# SCH_power_supply_7805_2026-06-21.net
KiCad netlist of a schematic drawn in EasyEDA
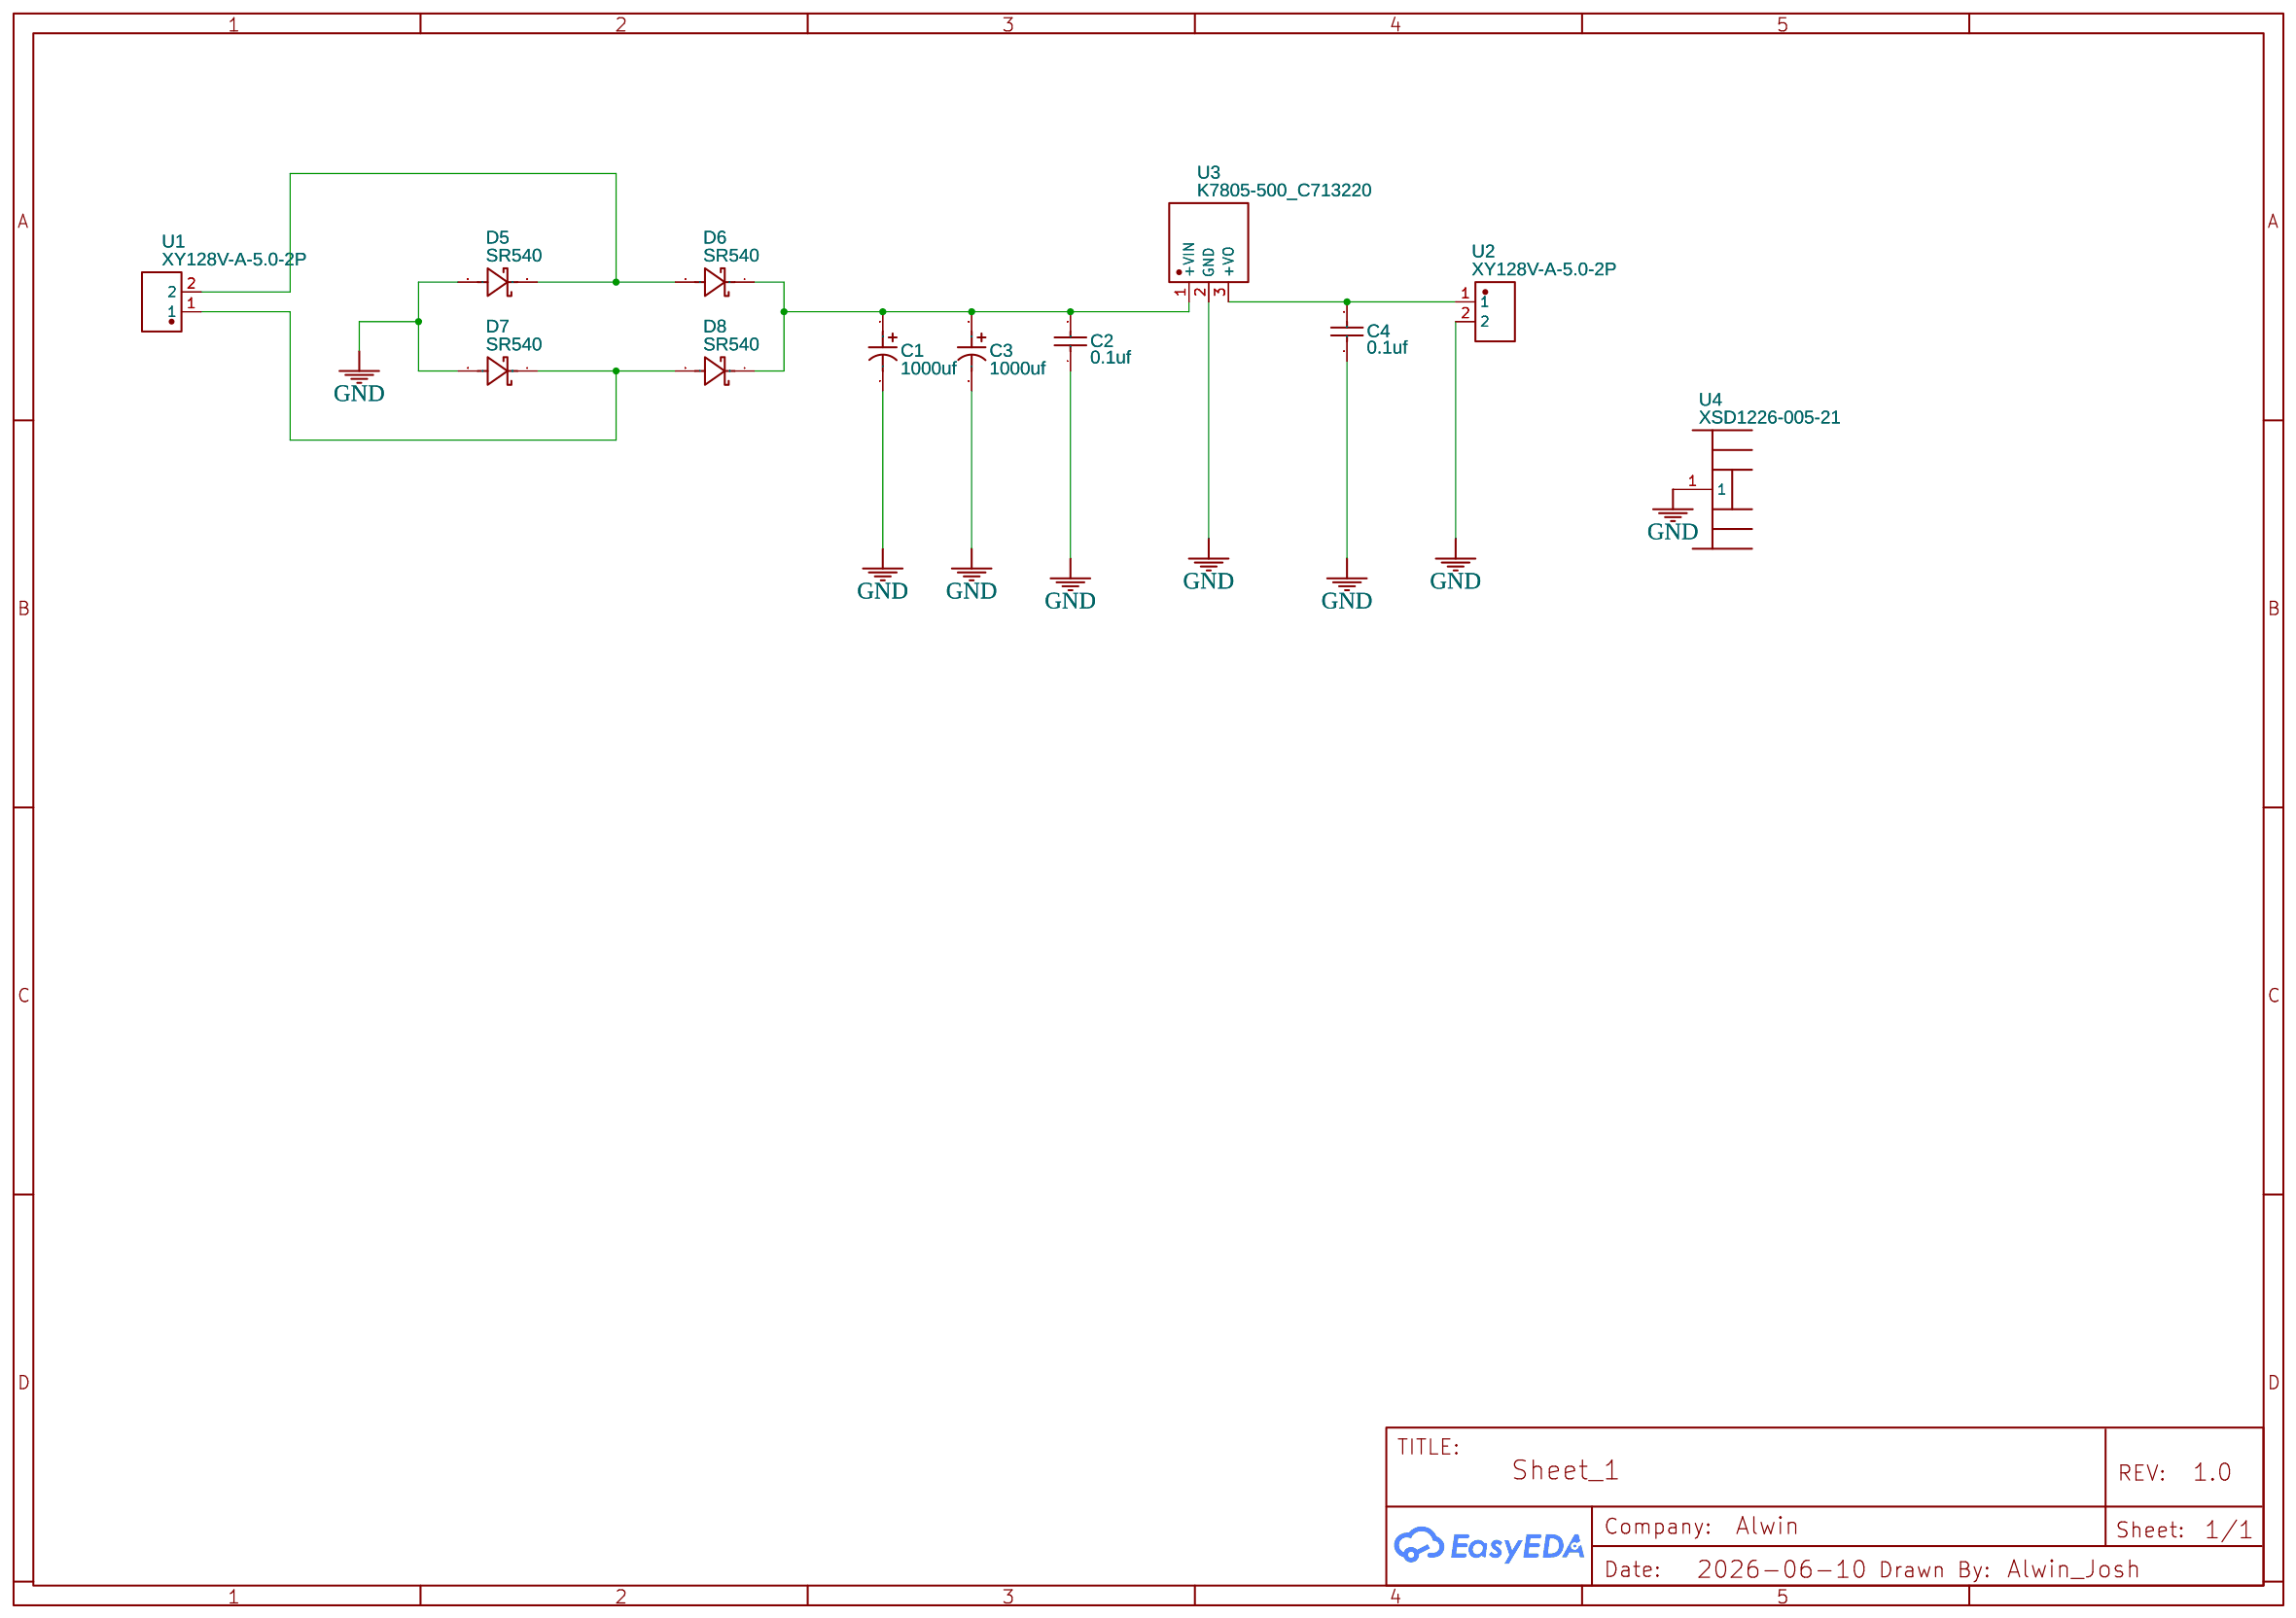
[diagram p0: schematic sheet]

(export (version "E")
  (design (tool "Eeschema 10.0.6"))
  (components
    (comp (ref "C1")
      (value "1000uf")
      (fields
        (field (name "Manufacturer Part") "RVT2A4R7M0607ZY")
        (field (name "Manufacturer") "ChengTao(诚韬)")
      )
      (libsource (lib "") (part "RVT2A4R7M0607ZY"))
    )
    (comp (ref "C2")
      (value "0.1uf")
      (fields (field (name "Manufacturer Part") "CT4-0805Y104M500") (field (name "Manufacturer") "LCSC"))
      (libsource (lib "") (part "0.1uf"))
    )
    (comp (ref "C3")
      (value "1000uf")
      (fields
        (field (name "Manufacturer Part") "RVT2A4R7M0607ZY")
        (field (name "Manufacturer") "ChengTao(诚韬)")
      )
      (libsource (lib "") (part "RVT2A4R7M0607ZY"))
    )
    (comp (ref "C4")
      (value "0.1uf")
      (fields (field (name "Manufacturer Part") "CT4-0805Y104M500") (field (name "Manufacturer") "LCSC"))
      (libsource (lib "") (part "0.1uf"))
    )
    (comp (ref "D5")
      (value "SR540")
      (fields (field (name "Manufacturer") "XUMAO(旭茂微)"))
      (libsource (lib "") (part "SR540_C22448098"))
    )
    (comp (ref "D6")
      (value "SR540")
      (fields (field (name "Manufacturer") "XUMAO(旭茂微)"))
      (libsource (lib "") (part "SR540_C22448098"))
    )
    (comp (ref "D7")
      (value "SR540")
      (fields (field (name "Manufacturer") "XUMAO(旭茂微)"))
      (libsource (lib "") (part "SR540_C22448098"))
    )
    (comp (ref "D8")
      (value "SR540")
      (fields (field (name "Manufacturer") "XUMAO(旭茂微)"))
      (libsource (lib "") (part "SR540_C22448098"))
    )
    (comp (ref "U1")
      (value "XY128V-A-5.0-2P")
      (fields (field (name "Manufacturer") "XINLAIYA(新莱亚)"))
      (libsource (lib "") (part "XY128V-A-5.0-2P"))
    )
    (comp (ref "U2")
      (value "XY128V-A-5.0-2P")
      (fields (field (name "Manufacturer") "XINLAIYA(新莱亚)"))
      (libsource (lib "") (part "XY128V-A-5.0-2P_1"))
    )
    (comp (ref "U3")
      (value "K7805-500_C713220")
      (fields (field (name "Manufacturer Part") "K7805-500") (field (name "Manufacturer") "rlt"))
      (libsource (lib "") (part "K7805-500_C713220"))
    )
    (comp (ref "U4")
      (value "XSD1226-005-21")
      (fields (field (name "Manufacturer") "XSD(鑫顺达)"))
      (libsource (lib "") (part "XSD1226-005-21"))
    )
  )
  (nets
    (net (code "1") (name "GND") (class "Default")
      (node (ref "C1") (pin "2") (pinfunction "2_2") (pintype "input"))
      (node (ref "C2") (pin "1") (pinfunction "1_1") (pintype "input"))
      (node (ref "C3") (pin "2") (pinfunction "2_2") (pintype "input"))
      (node (ref "C4") (pin "1") (pinfunction "1_1") (pintype "input"))
      (node (ref "D5") (pin "2") (pinfunction "A_2") (pintype "unspecified"))
      (node (ref "D7") (pin "2") (pinfunction "A_2") (pintype "unspecified"))
      (node (ref "U2") (pin "2") (pinfunction "2_2") (pintype "unspecified"))
      (node (ref "U3") (pin "2") (pinfunction "GND_2") (pintype "unspecified"))
      (node (ref "U4") (pin "1") (pinfunction "1_1") (pintype "unspecified"))
    )
    (net (code "2") (name "Net-(D5-C)") (class "Default")
      (node (ref "D5") (pin "1") (pinfunction "C_1") (pintype "unspecified"))
      (node (ref "D6") (pin "2") (pinfunction "A_2") (pintype "unspecified"))
      (node (ref "U1") (pin "2") (pinfunction "2_2") (pintype "unspecified"))
    )
    (net (code "3") (name "Net-(D6-C)") (class "Default")
      (node (ref "C1") (pin "1") (pinfunction "1_1") (pintype "input"))
      (node (ref "C2") (pin "2") (pinfunction "2_2") (pintype "input"))
      (node (ref "C3") (pin "1") (pinfunction "1_1") (pintype "input"))
      (node (ref "D6") (pin "1") (pinfunction "C_1") (pintype "unspecified"))
      (node (ref "D8") (pin "1") (pinfunction "C_1") (pintype "unspecified"))
      (node (ref "U3") (pin "1") (pinfunction "+VIN_1") (pintype "unspecified"))
    )
    (net (code "4") (name "Net-(D7-C)") (class "Default")
      (node (ref "D7") (pin "1") (pinfunction "C_1") (pintype "unspecified"))
      (node (ref "D8") (pin "2") (pinfunction "A_2") (pintype "unspecified"))
      (node (ref "U1") (pin "1") (pinfunction "1_1") (pintype "unspecified"))
    )
    (net (code "5") (name "Net-(U3-+VO)") (class "Default")
      (node (ref "C4") (pin "2") (pinfunction "2_2") (pintype "input"))
      (node (ref "U2") (pin "1") (pinfunction "1_1") (pintype "unspecified"))
      (node (ref "U3") (pin "3") (pinfunction "+VO_3") (pintype "unspecified"))
    )
  )
)
